# main.net
KiCad netlist of a schematic drawn in Altium Designer
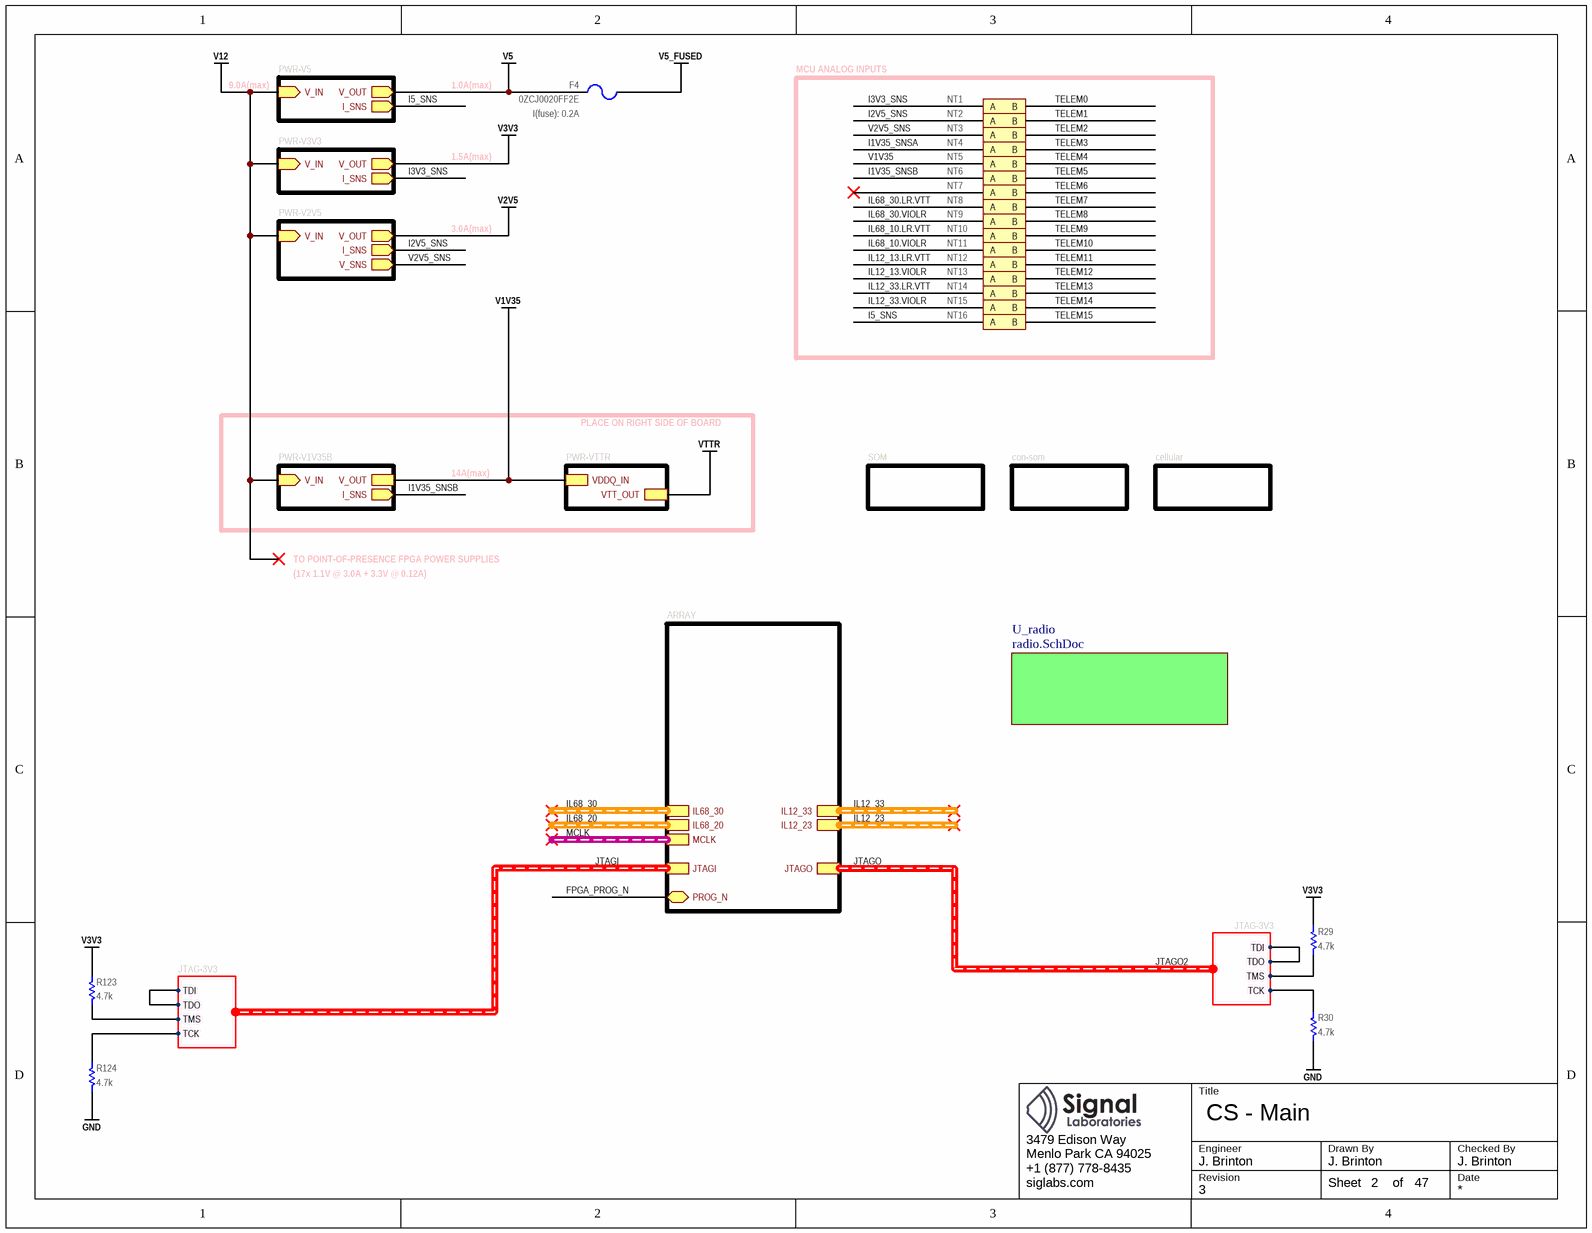
[diagram p0: main.SchDoc]

(export (version "E")
  (design (tool "Eeschema 10.0.6"))
  (components
    (comp (ref "F4")
      (value "0ZCJ0020FF2E")
      (footprint "generic:1206")
      (description "PTC Resettable Fuse, 0.2A, 30V, SMD 1206")
      (fields (field (name "MANUFACTURER") "Bell Fuse") (field (name "I(FUSE)") "0.2A"))
      (libsource (lib "bel-fuse") (part "0ZCJ0020FF2E"))
    )
    (comp (ref "NT1")
      (value "NET_TIE")
      (footprint "NET_TIE")
      (libsource (lib "copper_suicide") (part "NET_TIE"))
    )
    (comp (ref "NT2")
      (value "NET_TIE")
      (footprint "NET_TIE")
      (libsource (lib "copper_suicide") (part "NET_TIE"))
    )
    (comp (ref "NT3")
      (value "NET_TIE")
      (footprint "NET_TIE")
      (libsource (lib "copper_suicide") (part "NET_TIE"))
    )
    (comp (ref "NT4")
      (value "NET_TIE")
      (footprint "NET_TIE")
      (libsource (lib "copper_suicide") (part "NET_TIE"))
    )
    (comp (ref "NT5")
      (value "NET_TIE")
      (footprint "NET_TIE")
      (libsource (lib "copper_suicide") (part "NET_TIE"))
    )
    (comp (ref "NT6")
      (value "NET_TIE")
      (footprint "NET_TIE")
      (libsource (lib "copper_suicide") (part "NET_TIE"))
    )
    (comp (ref "NT7")
      (value "NET_TIE")
      (footprint "NET_TIE")
      (libsource (lib "copper_suicide") (part "NET_TIE"))
    )
    (comp (ref "NT8")
      (value "NET_TIE")
      (footprint "NET_TIE")
      (libsource (lib "copper_suicide") (part "NET_TIE"))
    )
    (comp (ref "NT9")
      (value "NET_TIE")
      (footprint "NET_TIE")
      (libsource (lib "copper_suicide") (part "NET_TIE"))
    )
    (comp (ref "NT10")
      (value "NET_TIE")
      (footprint "NET_TIE")
      (libsource (lib "copper_suicide") (part "NET_TIE"))
    )
    (comp (ref "NT11")
      (value "NET_TIE")
      (footprint "NET_TIE")
      (libsource (lib "copper_suicide") (part "NET_TIE"))
    )
    (comp (ref "NT12")
      (value "NET_TIE")
      (footprint "NET_TIE")
      (libsource (lib "copper_suicide") (part "NET_TIE"))
    )
    (comp (ref "NT13")
      (value "NET_TIE")
      (footprint "NET_TIE")
      (libsource (lib "copper_suicide") (part "NET_TIE"))
    )
    (comp (ref "NT14")
      (value "NET_TIE")
      (footprint "NET_TIE")
      (libsource (lib "copper_suicide") (part "NET_TIE"))
    )
    (comp (ref "NT15")
      (value "NET_TIE")
      (footprint "NET_TIE")
      (libsource (lib "copper_suicide") (part "NET_TIE"))
    )
    (comp (ref "NT16")
      (value "NET_TIE")
      (footprint "NET_TIE")
      (libsource (lib "copper_suicide") (part "NET_TIE"))
    )
    (comp (ref "R29")
      (value "4.7k")
      (footprint "RESC1005X40N")
      (description "Thick Film Resistor 4.7k ±1% 0.1W 75V 0402")
      (fields (field (name "TOLERANCE") "±1%") (field (name "MANUFACTURER") "Panasonic"))
      (libsource (lib "generic") (part "RES"))
    )
    (comp (ref "R30")
      (value "4.7k")
      (footprint "RESC1005X40N")
      (description "Thick Film Resistor 4.7k ±1% 0.1W 75V 0402")
      (fields (field (name "TOLERANCE") "±1%") (field (name "MANUFACTURER") "Panasonic"))
      (libsource (lib "generic") (part "RES"))
    )
    (comp (ref "R123")
      (value "4.7k")
      (footprint "RESC1005X40N")
      (description "Thick Film Resistor 4.7k ±1% 0.1W 75V 0402")
      (fields (field (name "TOLERANCE") "±1%") (field (name "MANUFACTURER") "Panasonic"))
      (libsource (lib "generic") (part "RES"))
    )
    (comp (ref "R124")
      (value "4.7k")
      (footprint "RESC1005X40N")
      (description "Thick Film Resistor 4.7k ±1% 0.1W 75V 0402")
      (fields (field (name "TOLERANCE") "±1%") (field (name "MANUFACTURER") "Panasonic"))
      (libsource (lib "generic") (part "RES"))
    )
  )
  (nets
    (net (code "9") (name "/I1V35_SNSA") (class "Default")
      (node (ref "NT4") (pin "A") (pinfunction "A_A") (pintype "passive"))
    )
    (net (code "10") (name "/I1V35_SNSB") (class "Default")
      (node (ref "NT6") (pin "A") (pinfunction "A_A") (pintype "passive"))
    )
    (net (code "11") (name "/I2V5_SNS") (class "Default")
      (node (ref "NT2") (pin "A") (pinfunction "A_A") (pintype "passive"))
    )
    (net (code "12") (name "/I3V3_SNS") (class "Default")
      (node (ref "NT1") (pin "A") (pinfunction "A_A") (pintype "passive"))
    )
    (net (code "13") (name "/I5_SNS") (class "Default")
      (node (ref "NT16") (pin "A") (pinfunction "A_A") (pintype "passive"))
    )
    (net (code "14") (name "/IL12_13.LR.VTT") (class "Default")
      (node (ref "NT12") (pin "A") (pinfunction "A_A") (pintype "passive"))
    )
    (net (code "15") (name "/IL12_13.VIOLR") (class "Default")
      (node (ref "NT13") (pin "A") (pinfunction "A_A") (pintype "passive"))
    )
    (net (code "16") (name "/IL12_33.LR.VTT") (class "Default")
      (node (ref "NT14") (pin "A") (pinfunction "A_A") (pintype "passive"))
    )
    (net (code "17") (name "/IL12_33.VIOLR") (class "Default")
      (node (ref "NT15") (pin "A") (pinfunction "A_A") (pintype "passive"))
    )
    (net (code "18") (name "/IL68_10.LR.VTT") (class "Default")
      (node (ref "NT10") (pin "A") (pinfunction "A_A") (pintype "passive"))
    )
    (net (code "19") (name "/IL68_10.VIOLR") (class "Default")
      (node (ref "NT11") (pin "A") (pinfunction "A_A") (pintype "passive"))
    )
    (net (code "20") (name "/IL68_30.LR.VTT") (class "Default")
      (node (ref "NT8") (pin "A") (pinfunction "A_A") (pintype "passive"))
    )
    (net (code "21") (name "/IL68_30.VIOLR") (class "Default")
      (node (ref "NT9") (pin "A") (pinfunction "A_A") (pintype "passive"))
    )
    (net (code "24") (name "/TELEM0") (class "Default")
      (node (ref "NT1") (pin "B") (pinfunction "B_B") (pintype "passive"))
    )
    (net (code "25") (name "/TELEM1") (class "Default")
      (node (ref "NT2") (pin "B") (pinfunction "B_B") (pintype "passive"))
    )
    (net (code "26") (name "/TELEM2") (class "Default")
      (node (ref "NT3") (pin "B") (pinfunction "B_B") (pintype "passive"))
    )
    (net (code "27") (name "/TELEM3") (class "Default")
      (node (ref "NT4") (pin "B") (pinfunction "B_B") (pintype "passive"))
    )
    (net (code "28") (name "/TELEM4") (class "Default")
      (node (ref "NT5") (pin "B") (pinfunction "B_B") (pintype "passive"))
    )
    (net (code "29") (name "/TELEM5") (class "Default")
      (node (ref "NT6") (pin "B") (pinfunction "B_B") (pintype "passive"))
    )
    (net (code "30") (name "/TELEM6") (class "Default")
      (node (ref "NT7") (pin "B") (pinfunction "B_B") (pintype "passive"))
    )
    (net (code "31") (name "/TELEM7") (class "Default")
      (node (ref "NT8") (pin "B") (pinfunction "B_B") (pintype "passive"))
    )
    (net (code "32") (name "/TELEM8") (class "Default")
      (node (ref "NT9") (pin "B") (pinfunction "B_B") (pintype "passive"))
    )
    (net (code "33") (name "/TELEM9") (class "Default")
      (node (ref "NT10") (pin "B") (pinfunction "B_B") (pintype "passive"))
    )
    (net (code "34") (name "/TELEM10") (class "Default")
      (node (ref "NT11") (pin "B") (pinfunction "B_B") (pintype "passive"))
    )
    (net (code "35") (name "/TELEM11") (class "Default")
      (node (ref "NT12") (pin "B") (pinfunction "B_B") (pintype "passive"))
    )
    (net (code "36") (name "/TELEM12") (class "Default")
      (node (ref "NT13") (pin "B") (pinfunction "B_B") (pintype "passive"))
    )
    (net (code "37") (name "/TELEM13") (class "Default")
      (node (ref "NT14") (pin "B") (pinfunction "B_B") (pintype "passive"))
    )
    (net (code "38") (name "/TELEM14") (class "Default")
      (node (ref "NT15") (pin "B") (pinfunction "B_B") (pintype "passive"))
    )
    (net (code "39") (name "/TELEM15") (class "Default")
      (node (ref "NT16") (pin "B") (pinfunction "B_B") (pintype "passive"))
    )
    (net (code "40") (name "/V2V5_SNS") (class "Default")
      (node (ref "NT3") (pin "A") (pinfunction "A_A") (pintype "passive"))
    )
    (net (code "46") (name "GND") (class "Default")
      (node (ref "R124") (pin "1") (pinfunction "1_1") (pintype "passive"))
      (node (ref "R30") (pin "1") (pinfunction "1_1") (pintype "passive"))
    )
    (net (code "47") (name "V1V35") (class "Default")
      (node (ref "NT5") (pin "A") (pinfunction "A_A") (pintype "passive"))
    )
    (net (code "49") (name "V3V3") (class "Default")
      (node (ref "R123") (pin "2") (pinfunction "2_2") (pintype "passive"))
      (node (ref "R29") (pin "2") (pinfunction "2_2") (pintype "passive"))
    )
    (net (code "50") (name "V5") (class "Default")
      (node (ref "F4") (pin "1") (pinfunction "1_1") (pintype "passive"))
    )
    (net (code "51") (name "V5_FUSED") (class "Default")
      (node (ref "F4") (pin "2") (pinfunction "2_2") (pintype "passive"))
    )
    (net (code "54") (name "unconnected-(NT7-PadA)") (class "Default")
      (node (ref "NT7") (pin "A") (pinfunction "A_A") (pintype "passive+no_connect"))
    )
    (net (code "55") (name "unconnected-(R29-Pad1)") (class "Default")
      (node (ref "R29") (pin "1") (pinfunction "1_1") (pintype "passive"))
    )
    (net (code "56") (name "unconnected-(R30-Pad2)") (class "Default")
      (node (ref "R30") (pin "2") (pinfunction "2_2") (pintype "passive"))
    )
    (net (code "57") (name "unconnected-(R123-Pad1)") (class "Default")
      (node (ref "R123") (pin "1") (pinfunction "1_1") (pintype "passive"))
    )
    (net (code "58") (name "unconnected-(R124-Pad2)") (class "Default")
      (node (ref "R124") (pin "2") (pinfunction "2_2") (pintype "passive"))
    )
  )
)
